# esq_ordenado.net
KiCad netlist of a schematic drawn in EAGLE
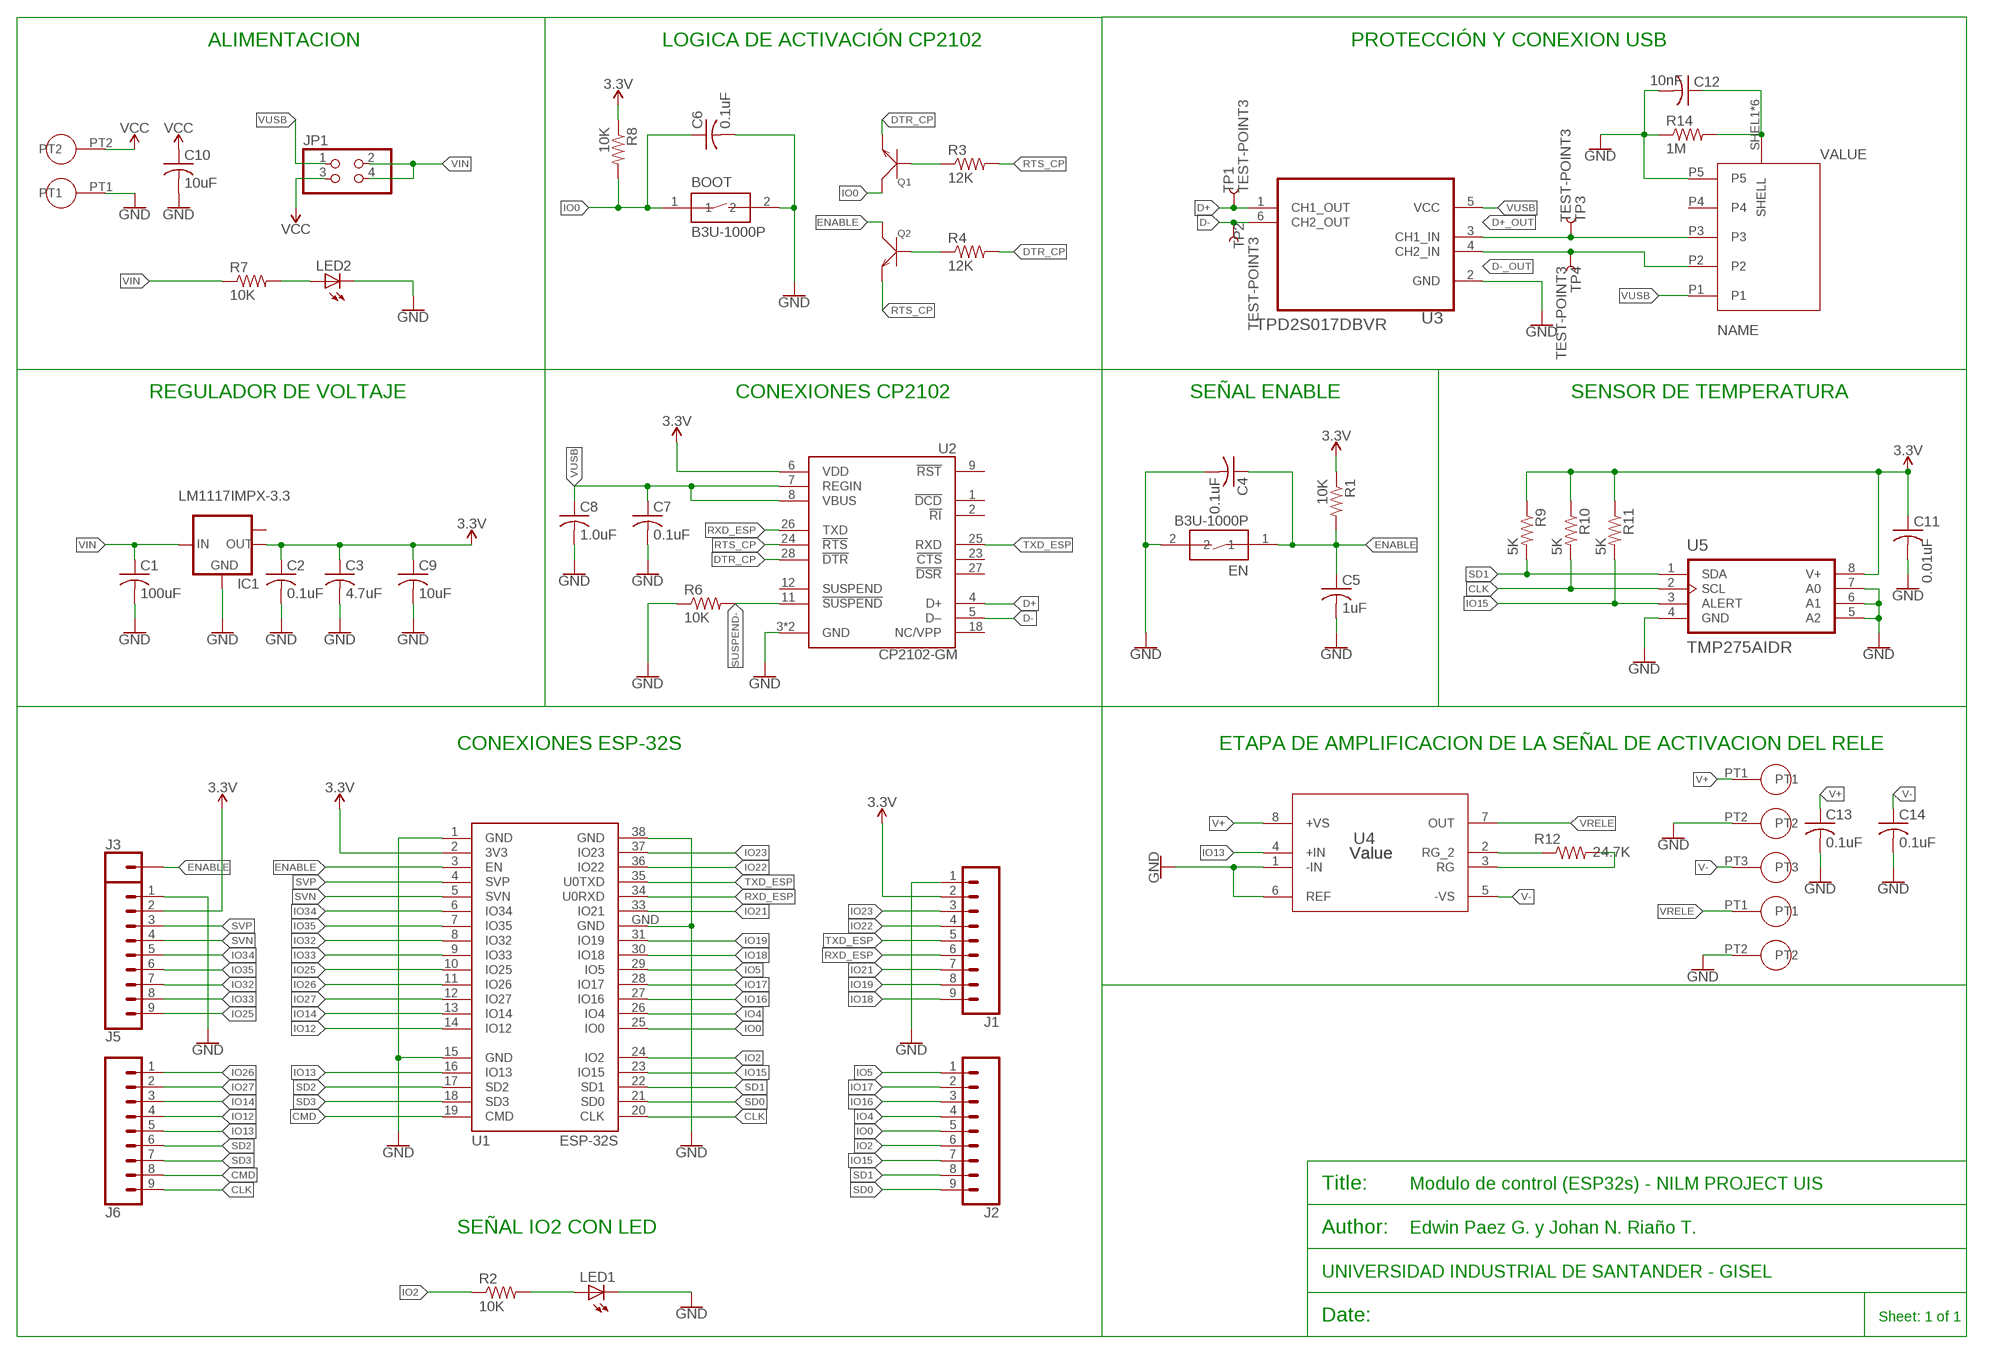
[diagram p0: schematic, sheet 1]

(export (version "E")
  (design (tool "Eeschema 10.0.6"))
  (components
    (comp (ref "BOOT")
      (value "B3U-1000P")
      (footprint "eagle-import:B3U-1000P")
      (fields
        (field (name "DIGI_KEY_PART_NUMBER") "SW1020CT-ND")
        (field (name "MANUFACTURER") "Omron Electronics Inc-EMC Div")
        (field (name "CREATED_BY") "PCBLayout.com")
      )
      (libsource (lib "eagle-import") (part "B3U-1000P"))
    )
    (comp (ref "C1")
      (value "100uF")
      (footprint "eagle-import:C0805")
      (libsource (lib "eagle-import") (part "C-USC0805"))
    )
    (comp (ref "C2")
      (value "0.1uF")
      (footprint "eagle-import:C0805")
      (libsource (lib "eagle-import") (part "C-USC0805"))
    )
    (comp (ref "C3")
      (value "4.7uF")
      (footprint "eagle-import:C0805")
      (libsource (lib "eagle-import") (part "C-USC0805"))
    )
    (comp (ref "C4")
      (value "0.1uF")
      (footprint "eagle-import:C0805")
      (libsource (lib "eagle-import") (part "C-USC0805"))
    )
    (comp (ref "C5")
      (value "1uF")
      (footprint "eagle-import:C0805")
      (libsource (lib "eagle-import") (part "C-USC0805"))
    )
    (comp (ref "C6")
      (value "0.1uF")
      (footprint "eagle-import:C0805")
      (libsource (lib "eagle-import") (part "C-USC0805"))
    )
    (comp (ref "C7")
      (value "0.1uF")
      (footprint "eagle-import:C0805")
      (libsource (lib "eagle-import") (part "C-USC0805"))
    )
    (comp (ref "C8")
      (value "1.0uF")
      (footprint "eagle-import:C0805")
      (libsource (lib "eagle-import") (part "C-USC0805"))
    )
    (comp (ref "C9")
      (value "10uF")
      (footprint "eagle-import:C0805")
      (libsource (lib "eagle-import") (part "C-USC0805"))
    )
    (comp (ref "C10")
      (value "10uF")
      (footprint "eagle-import:C0805")
      (libsource (lib "eagle-import") (part "C-USC0805"))
    )
    (comp (ref "C11")
      (value "0.01uF")
      (footprint "eagle-import:C0805")
      (libsource (lib "eagle-import") (part "C-USC0805"))
    )
    (comp (ref "C12")
      (value "10nF")
      (footprint "eagle-import:C0805")
      (libsource (lib "eagle-import") (part "C-USC0805"))
    )
    (comp (ref "C13")
      (value "0.1uF")
      (footprint "eagle-import:C0805")
      (libsource (lib "eagle-import") (part "C-USC0805"))
    )
    (comp (ref "C14")
      (value "0.1uF")
      (footprint "eagle-import:C0805")
      (libsource (lib "eagle-import") (part "C-USC0805"))
    )
    (comp (ref "EN")
      (value "B3U-1000P")
      (footprint "eagle-import:B3U-1000P")
      (fields
        (field (name "DIGI_KEY_PART_NUMBER") "SW1020CT-ND")
        (field (name "MANUFACTURER") "Omron Electronics Inc-EMC Div")
        (field (name "CREATED_BY") "PCBLayout.com")
      )
      (libsource (lib "eagle-import") (part "B3U-1000P"))
    )
    (comp (ref "IC1")
      (value "LM1117IMPX-3.3")
      (footprint "eagle-import:SOT223")
      (libsource (lib "eagle-import") (part "LM1117IMPX-3.3"))
    )
    (comp (ref "J1")
      (value "CONN_09")
      (footprint "eagle-import:1X09")
      (libsource (lib "eagle-import") (part "CONN_09"))
    )
    (comp (ref "J2")
      (value "CONN_09")
      (footprint "eagle-import:1X09")
      (libsource (lib "eagle-import") (part "CONN_09"))
    )
    (comp (ref "J3")
      (value "CONN_01")
      (footprint "eagle-import:1X01")
      (libsource (lib "eagle-import") (part "CONN_01"))
    )
    (comp (ref "J5")
      (value "CONN_09")
      (footprint "eagle-import:1X09")
      (libsource (lib "eagle-import") (part "CONN_09"))
    )
    (comp (ref "J6")
      (value "CONN_09")
      (footprint "eagle-import:1X09")
      (libsource (lib "eagle-import") (part "CONN_09"))
    )
    (comp (ref "JP1")
      (value "PINHD-2X2")
      (footprint "eagle-import:2X02")
      (libsource (lib "eagle-import") (part "PINHD-2X2"))
    )
    (comp (ref "LED1")
      (value "LEDCHIPLED_0805")
      (footprint "eagle-import:CHIPLED_0805")
      (libsource (lib "eagle-import") (part "LEDCHIPLED_0805"))
    )
    (comp (ref "LED2")
      (value "LEDCHIPLED_0805")
      (footprint "eagle-import:CHIPLED_0805")
      (libsource (lib "eagle-import") (part "LEDCHIPLED_0805"))
    )
    (comp (ref "Q1")
      (value "SMD-TRANSISTORS-NPN-25V-500MW(SOT-23)")
      (footprint "eagle-import:SOT-23")
      (fields (field (name "MF") "Recom Power") (field (name "MP") "S8050"))
      (libsource (lib "eagle-import") (part "SMD-TRANSISTORS-NPN-25V-500MW(SOT-23)"))
    )
    (comp (ref "Q2")
      (value "SMD-TRANSISTORS-NPN-25V-500MW(SOT-23)")
      (footprint "eagle-import:SOT-23")
      (fields (field (name "MF") "Recom Power") (field (name "MP") "S8050"))
      (libsource (lib "eagle-import") (part "SMD-TRANSISTORS-NPN-25V-500MW(SOT-23)"))
    )
    (comp (ref "R1")
      (value "10K")
      (footprint "eagle-import:R0805")
      (libsource (lib "eagle-import") (part "R-US_R0805"))
    )
    (comp (ref "R2")
      (value "10K")
      (footprint "eagle-import:R0805")
      (libsource (lib "eagle-import") (part "R-US_R0805"))
    )
    (comp (ref "R3")
      (value "12K")
      (footprint "eagle-import:R0805")
      (libsource (lib "eagle-import") (part "R-US_R0805"))
    )
    (comp (ref "R4")
      (value "12K")
      (footprint "eagle-import:R0805")
      (libsource (lib "eagle-import") (part "R-US_R0805"))
    )
    (comp (ref "R6")
      (value "10K")
      (footprint "eagle-import:R0805")
      (libsource (lib "eagle-import") (part "R-US_R0805"))
    )
    (comp (ref "R7")
      (value "10K")
      (footprint "eagle-import:R0805")
      (libsource (lib "eagle-import") (part "R-US_R0805"))
    )
    (comp (ref "R8")
      (value "10K")
      (footprint "eagle-import:R0805")
      (libsource (lib "eagle-import") (part "R-US_R0805"))
    )
    (comp (ref "R9")
      (value "5K")
      (footprint "eagle-import:R0805")
      (libsource (lib "eagle-import") (part "R-US_R0805"))
    )
    (comp (ref "R10")
      (value "5K")
      (footprint "eagle-import:R0805")
      (libsource (lib "eagle-import") (part "R-US_R0805"))
    )
    (comp (ref "R11")
      (value "5K")
      (footprint "eagle-import:R0805")
      (libsource (lib "eagle-import") (part "R-US_R0805"))
    )
    (comp (ref "R12")
      (value "24.7K")
      (footprint "eagle-import:R0805")
      (libsource (lib "eagle-import") (part "R-US_R0805"))
    )
    (comp (ref "R14")
      (value "1M")
      (footprint "eagle-import:R0805")
      (libsource (lib "eagle-import") (part "R-US_R0805"))
    )
    (comp (ref "TP1")
      (value "TEST-POINT3")
      (footprint "eagle-import:PAD.03X.03")
      (libsource (lib "eagle-import") (part "TEST-POINT3"))
    )
    (comp (ref "TP2")
      (value "TEST-POINT3")
      (footprint "eagle-import:PAD.03X.03")
      (libsource (lib "eagle-import") (part "TEST-POINT3"))
    )
    (comp (ref "TP3")
      (value "TEST-POINT3")
      (footprint "eagle-import:PAD.03X.03")
      (libsource (lib "eagle-import") (part "TEST-POINT3"))
    )
    (comp (ref "TP4")
      (value "TEST-POINT3")
      (footprint "eagle-import:PAD.03X.03")
      (libsource (lib "eagle-import") (part "TEST-POINT3"))
    )
    (comp (ref "U$1")
      (value "MICRO_USB_B-AMPHENOL(10118192)")
      (footprint "eagle-import:MICRO_B_10118192")
      (libsource (lib "eagle-import") (part "MICRO_USB_B-AMPHENOL(10118192)"))
    )
    (comp (ref "U$2")
      (value "PT2,5/2-5,0")
      (footprint "eagle-import:PT2,5_2-5,0")
      (libsource (lib "eagle-import") (part "PT2,5/2-5,0"))
    )
    (comp (ref "U$3")
      (value "PT2,5/2-5,0")
      (footprint "eagle-import:PT2,5_2-5,0")
      (libsource (lib "eagle-import") (part "PT2,5/2-5,0"))
    )
    (comp (ref "U$4")
      (value "PT2,5/3-5,0")
      (footprint "eagle-import:PT2,5_3-5,0")
      (libsource (lib "eagle-import") (part "PT2,5/3-5,0"))
    )
    (comp (ref "U1")
      (value "ESP-32S")
      (footprint "eagle-import:ESP-32S")
      (libsource (lib "eagle-import") (part "ESP-32S"))
    )
    (comp (ref "U2")
      (value "CP2102-GM")
      (footprint "eagle-import:QFN50P500X500X100-29N")
      (fields (field (name "MF") "Silicon Labs"))
      (libsource (lib "eagle-import") (part "CP2102-GM"))
    )
    (comp (ref "U3")
      (value "TPD2S017DBVR")
      (footprint "eagle-import:SOT95P280X145-6N")
      (fields (field (name "DIGI-KEY_PART_NUMBER") "296-25216-1-ND") (field (name "MF") "Texas Instruments"))
      (libsource (lib "eagle-import") (part "TPD2S017DBVR"))
    )
    (comp (ref "U4")
      (value "Value")
      (footprint "eagle-import:D0008A_M")
      (fields (field (name "MANUFACTURER") "Texas Instruments") (field (name "PARTNUMBER") "INA821ID"))
      (libsource (lib "eagle-import") (part "INA821IDD0008A_M"))
    )
    (comp (ref "U5")
      (value "TMP275AIDR")
      (footprint "eagle-import:TMP275AIDR")
      (fields
        (field (name "DIGIKEY_PART_NUMBER") "296-39296-2-ND")
        (field (name "MANUFACTURER") "Texas Instruments")
        (field (name "CREATED_BY") "PCBLayout.com")
      )
      (libsource (lib "eagle-import") (part "TMP275AIDR"))
    )
  )
  (nets
    (net (code "1") (name "3.3V") (class "Default")
      (node (ref "C11") (pin "1") (pinfunction "1_1") (pintype "passive"))
      (node (ref "C2") (pin "1") (pinfunction "1_1") (pintype "passive"))
      (node (ref "C3") (pin "1") (pinfunction "1_1") (pintype "passive"))
      (node (ref "C9") (pin "1") (pinfunction "1_1") (pintype "passive"))
      (node (ref "IC1") (pin "2") (pinfunction "OUT_2") (pintype "passive"))
      (node (ref "J1") (pin "2") (pinfunction "2_2") (pintype "passive"))
      (node (ref "J5") (pin "2") (pinfunction "2_2") (pintype "passive"))
      (node (ref "R1") (pin "1") (pinfunction "1_1") (pintype "passive"))
      (node (ref "R10") (pin "1") (pinfunction "1_1") (pintype "passive"))
      (node (ref "R11") (pin "1") (pinfunction "1_1") (pintype "passive"))
      (node (ref "R8") (pin "1") (pinfunction "1_1") (pintype "passive"))
      (node (ref "R9") (pin "1") (pinfunction "1_1") (pintype "passive"))
      (node (ref "U1") (pin "2") (pinfunction "3V3_2") (pintype "power_in"))
      (node (ref "U2") (pin "6") (pinfunction "VDD_6") (pintype "power_in"))
      (node (ref "U5") (pin "8") (pinfunction "V+_8") (pintype "input"))
    )
    (net (code "2") (name "CLK") (class "Default")
      (node (ref "J6") (pin "9") (pinfunction "9_9") (pintype "passive"))
      (node (ref "R10") (pin "2") (pinfunction "2_2") (pintype "passive"))
      (node (ref "U1") (pin "20") (pinfunction "CLK_20") (pintype "bidirectional"))
      (node (ref "U5") (pin "2") (pinfunction "SCL_2") (pintype "input"))
    )
    (net (code "3") (name "CMD") (class "Default")
      (node (ref "J6") (pin "8") (pinfunction "8_8") (pintype "passive"))
      (node (ref "U1") (pin "19") (pinfunction "CMD_19") (pintype "bidirectional"))
    )
    (net (code "4") (name "D+") (class "Default")
      (node (ref "TP1") (pin "P$1") (pinfunction "1_P$1") (pintype "bidirectional"))
      (node (ref "U2") (pin "4") (pinfunction "D+_4") (pintype "bidirectional"))
      (node (ref "U3") (pin "1") (pinfunction "CH1_OUT_1") (pintype "output"))
    )
    (net (code "5") (name "D+_OUT") (class "Default")
      (node (ref "TP3") (pin "P$1") (pinfunction "1_P$1") (pintype "bidirectional"))
      (node (ref "U$1") (pin "P3") (pinfunction "P3_P3") (pintype "bidirectional"))
      (node (ref "U3") (pin "3") (pinfunction "CH1_IN_3") (pintype "input"))
    )
    (net (code "6") (name "D-") (class "Default")
      (node (ref "TP2") (pin "P$1") (pinfunction "1_P$1") (pintype "bidirectional"))
      (node (ref "U2") (pin "5") (pinfunction "D–_5") (pintype "bidirectional"))
      (node (ref "U3") (pin "6") (pinfunction "CH2_OUT_6") (pintype "output"))
    )
    (net (code "7") (name "D-_OUT") (class "Default")
      (node (ref "TP4") (pin "P$1") (pinfunction "1_P$1") (pintype "bidirectional"))
      (node (ref "U$1") (pin "P2") (pinfunction "P2_P2") (pintype "bidirectional"))
      (node (ref "U3") (pin "4") (pinfunction "CH2_IN_4") (pintype "input"))
    )
    (net (code "8") (name "DTR_CP") (class "Default")
      (node (ref "Q1") (pin "2") (pinfunction "E_2") (pintype "passive"))
      (node (ref "R4") (pin "2") (pinfunction "2_2") (pintype "passive"))
      (node (ref "U2") (pin "28") (pinfunction "~{DTR}_28") (pintype "output"))
    )
    (net (code "9") (name "ENABLE") (class "Default")
      (node (ref "C4") (pin "1") (pinfunction "1_1") (pintype "passive"))
      (node (ref "C5") (pin "1") (pinfunction "1_1") (pintype "passive"))
      (node (ref "EN") (pin "1") (pinfunction "1_1") (pintype "passive"))
      (node (ref "J3") (pin "1") (pinfunction "1_1") (pintype "passive"))
      (node (ref "Q2") (pin "3") (pinfunction "C_3") (pintype "passive"))
      (node (ref "R1") (pin "2") (pinfunction "2_2") (pintype "passive"))
      (node (ref "U1") (pin "3") (pinfunction "EN_3") (pintype "input"))
    )
    (net (code "10") (name "GND") (class "Default")
      (node (ref "BOOT") (pin "2") (pinfunction "2_2") (pintype "passive"))
      (node (ref "C1") (pin "2") (pinfunction "2_2") (pintype "passive"))
      (node (ref "C10") (pin "2") (pinfunction "2_2") (pintype "passive"))
      (node (ref "C11") (pin "2") (pinfunction "2_2") (pintype "passive"))
      (node (ref "C12") (pin "2") (pinfunction "2_2") (pintype "passive"))
      (node (ref "C13") (pin "2") (pinfunction "2_2") (pintype "passive"))
      (node (ref "C14") (pin "2") (pinfunction "2_2") (pintype "passive"))
      (node (ref "C2") (pin "2") (pinfunction "2_2") (pintype "passive"))
      (node (ref "C3") (pin "2") (pinfunction "2_2") (pintype "passive"))
      (node (ref "C4") (pin "2") (pinfunction "2_2") (pintype "passive"))
      (node (ref "C5") (pin "2") (pinfunction "2_2") (pintype "passive"))
      (node (ref "C6") (pin "2") (pinfunction "2_2") (pintype "passive"))
      (node (ref "C7") (pin "2") (pinfunction "2_2") (pintype "passive"))
      (node (ref "C8") (pin "2") (pinfunction "2_2") (pintype "passive"))
      (node (ref "C9") (pin "2") (pinfunction "2_2") (pintype "passive"))
      (node (ref "EN") (pin "2") (pinfunction "2_2") (pintype "passive"))
      (node (ref "IC1") (pin "1") (pinfunction "GND_1") (pintype "input"))
      (node (ref "J1") (pin "1") (pinfunction "1_1") (pintype "passive"))
      (node (ref "J5") (pin "1") (pinfunction "1_1") (pintype "passive"))
      (node (ref "LED1") (pin "C") (pinfunction "C_C") (pintype "passive"))
      (node (ref "LED2") (pin "C") (pinfunction "C_C") (pintype "passive"))
      (node (ref "R14") (pin "1") (pinfunction "1_1") (pintype "passive"))
      (node (ref "R6") (pin "1") (pinfunction "1_1") (pintype "passive"))
      (node (ref "U$1") (pin "P5") (pinfunction "P5_P5") (pintype "bidirectional"))
      (node (ref "U$2") (pin "PT1") (pinfunction "PT1_PT1") (pintype "bidirectional"))
      (node (ref "U$3") (pin "PT2") (pinfunction "PT2_PT2") (pintype "bidirectional"))
      (node (ref "U$4") (pin "PT2") (pinfunction "PT2_PT2") (pintype "bidirectional"))
      (node (ref "U1") (pin "1") (pinfunction "GND_1") (pintype "power_in"))
      (node (ref "U1") (pin "15") (pinfunction "GND_15") (pintype "power_in"))
      (node (ref "U1") (pin "38") (pinfunction "GND_38") (pintype "power_in"))
      (node (ref "U1") (pin "GND") (pinfunction "GND_GND") (pintype "power_in"))
      (node (ref "U2") (pin "29") (pinfunction "GND_29") (pintype "power_in"))
      (node (ref "U2") (pin "3") (pinfunction "GND_3") (pintype "power_in"))
      (node (ref "U3") (pin "2") (pinfunction "GND_2") (pintype "passive"))
      (node (ref "U4") (pin "1") (pinfunction "-IN_1") (pintype "input"))
      (node (ref "U4") (pin "6") (pinfunction "REF_6") (pintype "input"))
      (node (ref "U5") (pin "4") (pinfunction "GND_4") (pintype "power_in"))
      (node (ref "U5") (pin "5") (pinfunction "A2_5") (pintype "input"))
      (node (ref "U5") (pin "6") (pinfunction "A1_6") (pintype "input"))
      (node (ref "U5") (pin "7") (pinfunction "A0_7") (pintype "input"))
    )
    (net (code "11") (name "IO0") (class "Default")
      (node (ref "BOOT") (pin "1") (pinfunction "1_1") (pintype "passive"))
      (node (ref "C6") (pin "1") (pinfunction "1_1") (pintype "passive"))
      (node (ref "J2") (pin "5") (pinfunction "5_5") (pintype "passive"))
      (node (ref "Q1") (pin "3") (pinfunction "C_3") (pintype "passive"))
      (node (ref "R8") (pin "2") (pinfunction "2_2") (pintype "passive"))
      (node (ref "U1") (pin "25") (pinfunction "IO0_25") (pintype "bidirectional"))
    )
    (net (code "12") (name "IO2") (class "Default")
      (node (ref "J2") (pin "6") (pinfunction "6_6") (pintype "passive"))
      (node (ref "R2") (pin "1") (pinfunction "1_1") (pintype "passive"))
      (node (ref "U1") (pin "24") (pinfunction "IO2_24") (pintype "bidirectional"))
    )
    (net (code "13") (name "IO4") (class "Default")
      (node (ref "J2") (pin "4") (pinfunction "4_4") (pintype "passive"))
      (node (ref "U1") (pin "26") (pinfunction "IO4_26") (pintype "bidirectional"))
    )
    (net (code "14") (name "IO5") (class "Default")
      (node (ref "J2") (pin "1") (pinfunction "1_1") (pintype "passive"))
      (node (ref "U1") (pin "29") (pinfunction "IO5_29") (pintype "bidirectional"))
    )
    (net (code "15") (name "IO12") (class "Default")
      (node (ref "J6") (pin "4") (pinfunction "4_4") (pintype "passive"))
      (node (ref "U1") (pin "14") (pinfunction "IO12_14") (pintype "bidirectional"))
    )
    (net (code "16") (name "IO13") (class "Default")
      (node (ref "J6") (pin "5") (pinfunction "5_5") (pintype "passive"))
      (node (ref "U1") (pin "16") (pinfunction "IO13_16") (pintype "bidirectional"))
      (node (ref "U4") (pin "4") (pinfunction "+IN_4") (pintype "input"))
    )
    (net (code "17") (name "IO14") (class "Default")
      (node (ref "J6") (pin "3") (pinfunction "3_3") (pintype "passive"))
      (node (ref "U1") (pin "13") (pinfunction "IO14_13") (pintype "bidirectional"))
    )
    (net (code "18") (name "IO15") (class "Default")
      (node (ref "J2") (pin "7") (pinfunction "7_7") (pintype "passive"))
      (node (ref "R11") (pin "2") (pinfunction "2_2") (pintype "passive"))
      (node (ref "U1") (pin "23") (pinfunction "IO15_23") (pintype "bidirectional"))
      (node (ref "U5") (pin "3") (pinfunction "ALERT_3") (pintype "output"))
    )
    (net (code "19") (name "IO16") (class "Default")
      (node (ref "J2") (pin "3") (pinfunction "3_3") (pintype "passive"))
      (node (ref "U1") (pin "27") (pinfunction "IO16_27") (pintype "bidirectional"))
    )
    (net (code "20") (name "IO17") (class "Default")
      (node (ref "J2") (pin "2") (pinfunction "2_2") (pintype "passive"))
      (node (ref "U1") (pin "28") (pinfunction "IO17_28") (pintype "bidirectional"))
    )
    (net (code "21") (name "IO18") (class "Default")
      (node (ref "J1") (pin "9") (pinfunction "9_9") (pintype "passive"))
      (node (ref "U1") (pin "30") (pinfunction "IO18_30") (pintype "bidirectional"))
    )
    (net (code "22") (name "IO19") (class "Default")
      (node (ref "J1") (pin "8") (pinfunction "8_8") (pintype "passive"))
      (node (ref "U1") (pin "31") (pinfunction "IO19_31") (pintype "bidirectional"))
    )
    (net (code "23") (name "IO21") (class "Default")
      (node (ref "J1") (pin "7") (pinfunction "7_7") (pintype "passive"))
      (node (ref "U1") (pin "33") (pinfunction "IO21_33") (pintype "bidirectional"))
    )
    (net (code "24") (name "IO22") (class "Default")
      (node (ref "J1") (pin "4") (pinfunction "4_4") (pintype "passive"))
      (node (ref "U1") (pin "36") (pinfunction "IO22_36") (pintype "bidirectional"))
    )
    (net (code "25") (name "IO23") (class "Default")
      (node (ref "J1") (pin "3") (pinfunction "3_3") (pintype "passive"))
      (node (ref "U1") (pin "37") (pinfunction "IO23_37") (pintype "bidirectional"))
    )
    (net (code "26") (name "IO25") (class "Default")
      (node (ref "J5") (pin "9") (pinfunction "9_9") (pintype "passive"))
      (node (ref "U1") (pin "10") (pinfunction "IO25_10") (pintype "bidirectional"))
    )
    (net (code "27") (name "IO26") (class "Default")
      (node (ref "J6") (pin "1") (pinfunction "1_1") (pintype "passive"))
      (node (ref "U1") (pin "11") (pinfunction "IO26_11") (pintype "bidirectional"))
    )
    (net (code "28") (name "IO27") (class "Default")
      (node (ref "J6") (pin "2") (pinfunction "2_2") (pintype "passive"))
      (node (ref "U1") (pin "12") (pinfunction "IO27_12") (pintype "bidirectional"))
    )
    (net (code "29") (name "IO32") (class "Default")
      (node (ref "J5") (pin "7") (pinfunction "7_7") (pintype "passive"))
      (node (ref "U1") (pin "8") (pinfunction "IO32_8") (pintype "bidirectional"))
    )
    (net (code "30") (name "IO33") (class "Default")
      (node (ref "J5") (pin "8") (pinfunction "8_8") (pintype "passive"))
      (node (ref "U1") (pin "9") (pinfunction "IO33_9") (pintype "bidirectional"))
    )
    (net (code "31") (name "IO34") (class "Default")
      (node (ref "J5") (pin "5") (pinfunction "5_5") (pintype "passive"))
      (node (ref "U1") (pin "6") (pinfunction "IO34_6") (pintype "bidirectional"))
    )
    (net (code "32") (name "IO35") (class "Default")
      (node (ref "J5") (pin "6") (pinfunction "6_6") (pintype "passive"))
      (node (ref "U1") (pin "7") (pinfunction "IO35_7") (pintype "bidirectional"))
    )
    (net (code "33") (name "Net-(C12-Pad1)") (class "Default")
      (node (ref "C12") (pin "1") (pinfunction "1_1") (pintype "passive"))
      (node (ref "R14") (pin "2") (pinfunction "2_2") (pintype "passive"))
      (node (ref "U$1") (pin "SHEL1") (pinfunction "SHELL_SHEL1") (pintype "bidirectional"))
      (node (ref "U$1") (pin "SHEL2") (pinfunction "SHELL_SHEL2") (pintype "bidirectional"))
      (node (ref "U$1") (pin "SHEL3") (pinfunction "SHELL_SHEL3") (pintype "bidirectional"))
      (node (ref "U$1") (pin "SHEL4") (pinfunction "SHELL_SHEL4") (pintype "bidirectional"))
      (node (ref "U$1") (pin "SHEL5") (pinfunction "SHELL_SHEL5") (pintype "bidirectional"))
      (node (ref "U$1") (pin "SHEL6") (pinfunction "SHELL_SHEL6") (pintype "bidirectional"))
    )
    (net (code "34") (name "Net-(LED1-PadA)") (class "Default")
      (node (ref "LED1") (pin "A") (pinfunction "A_A") (pintype "passive"))
      (node (ref "R2") (pin "2") (pinfunction "2_2") (pintype "passive"))
    )
    (net (code "35") (name "Net-(LED2-PadA)") (class "Default")
      (node (ref "LED2") (pin "A") (pinfunction "A_A") (pintype "passive"))
      (node (ref "R7") (pin "2") (pinfunction "2_2") (pintype "passive"))
    )
    (net (code "36") (name "Net-(Q1-B)") (class "Default")
      (node (ref "Q1") (pin "1") (pinfunction "B_1") (pintype "passive"))
      (node (ref "R3") (pin "1") (pinfunction "1_1") (pintype "passive"))
    )
    (net (code "37") (name "Net-(Q2-B)") (class "Default")
      (node (ref "Q2") (pin "1") (pinfunction "B_1") (pintype "passive"))
      (node (ref "R4") (pin "1") (pinfunction "1_1") (pintype "passive"))
    )
    (net (code "38") (name "Net-(U4-RG)") (class "Default")
      (node (ref "R12") (pin "2") (pinfunction "2_2") (pintype "passive"))
      (node (ref "U4") (pin "3") (pinfunction "RG_3") (pintype "input"))
    )
    (net (code "39") (name "Net-(U4-RG_2)") (class "Default")
      (node (ref "R12") (pin "1") (pinfunction "1_1") (pintype "passive"))
      (node (ref "U4") (pin "2") (pinfunction "RG_2_2") (pintype "input"))
    )
    (net (code "40") (name "RTS_CP") (class "Default")
      (node (ref "Q2") (pin "2") (pinfunction "E_2") (pintype "passive"))
      (node (ref "R3") (pin "2") (pinfunction "2_2") (pintype "passive"))
      (node (ref "U2") (pin "24") (pinfunction "~{RTS}_24") (pintype "output"))
    )
    (net (code "41") (name "RXD_ESP") (class "Default")
      (node (ref "J1") (pin "6") (pinfunction "6_6") (pintype "passive"))
      (node (ref "U1") (pin "34") (pinfunction "U0RXD_34") (pintype "bidirectional"))
      (node (ref "U2") (pin "26") (pinfunction "TXD_26") (pintype "output"))
    )
    (net (code "42") (name "SD0") (class "Default")
      (node (ref "J2") (pin "9") (pinfunction "9_9") (pintype "passive"))
      (node (ref "U1") (pin "21") (pinfunction "SD0_21") (pintype "bidirectional"))
    )
    (net (code "43") (name "SD1") (class "Default")
      (node (ref "J2") (pin "8") (pinfunction "8_8") (pintype "passive"))
      (node (ref "R9") (pin "2") (pinfunction "2_2") (pintype "passive"))
      (node (ref "U1") (pin "22") (pinfunction "SD1_22") (pintype "bidirectional"))
      (node (ref "U5") (pin "1") (pinfunction "SDA_1") (pintype "bidirectional"))
    )
    (net (code "44") (name "SD2") (class "Default")
      (node (ref "J6") (pin "6") (pinfunction "6_6") (pintype "passive"))
      (node (ref "U1") (pin "17") (pinfunction "SD2_17") (pintype "bidirectional"))
    )
    (net (code "45") (name "SD3") (class "Default")
      (node (ref "J6") (pin "7") (pinfunction "7_7") (pintype "passive"))
      (node (ref "U1") (pin "18") (pinfunction "SD3_18") (pintype "bidirectional"))
    )
    (net (code "46") (name "SUSPEND-") (class "Default")
      (node (ref "R6") (pin "2") (pinfunction "2_2") (pintype "passive"))
      (node (ref "U2") (pin "11") (pinfunction "~{SUSPEND}_11") (pintype "output"))
    )
    (net (code "47") (name "SVN") (class "Default")
      (node (ref "J5") (pin "4") (pinfunction "4_4") (pintype "passive"))
      (node (ref "U1") (pin "5") (pinfunction "SVN_5") (pintype "bidirectional"))
    )
    (net (code "48") (name "SVP") (class "Default")
      (node (ref "J5") (pin "3") (pinfunction "3_3") (pintype "passive"))
      (node (ref "U1") (pin "4") (pinfunction "SVP_4") (pintype "bidirectional"))
    )
    (net (code "49") (name "TXD_ESP") (class "Default")
      (node (ref "J1") (pin "5") (pinfunction "5_5") (pintype "passive"))
      (node (ref "U1") (pin "35") (pinfunction "U0TXD_35") (pintype "bidirectional"))
      (node (ref "U2") (pin "25") (pinfunction "RXD_25") (pintype "input"))
    )
    (net (code "50") (name "V+") (class "Default")
      (node (ref "C13") (pin "1") (pinfunction "1_1") (pintype "passive"))
      (node (ref "U$4") (pin "PT1") (pinfunction "PT1_PT1") (pintype "bidirectional"))
      (node (ref "U4") (pin "8") (pinfunction "+VS_8") (pintype "power_in"))
    )
    (net (code "51") (name "V-") (class "Default")
      (node (ref "C14") (pin "1") (pinfunction "1_1") (pintype "passive"))
      (node (ref "U$4") (pin "PT3") (pinfunction "PT3_PT3") (pintype "bidirectional"))
      (node (ref "U4") (pin "5") (pinfunction "-VS_5") (pintype "power_in"))
    )
    (net (code "52") (name "VCC") (class "Default")
      (node (ref "C10") (pin "1") (pinfunction "1_1") (pintype "passive"))
      (node (ref "JP1") (pin "3") (pinfunction "3_3") (pintype "passive"))
      (node (ref "U$2") (pin "PT2") (pinfunction "PT2_PT2") (pintype "bidirectional"))
    )
    (net (code "53") (name "VIN") (class "Default")
      (node (ref "C1") (pin "1") (pinfunction "1_1") (pintype "passive"))
      (node (ref "IC1") (pin "3") (pinfunction "IN_3") (pintype "input"))
      (node (ref "JP1") (pin "2") (pinfunction "2_2") (pintype "passive"))
      (node (ref "JP1") (pin "4") (pinfunction "4_4") (pintype "passive"))
      (node (ref "R7") (pin "1") (pinfunction "1_1") (pintype "passive"))
    )
    (net (code "54") (name "VRELE") (class "Default")
      (node (ref "U$3") (pin "PT1") (pinfunction "PT1_PT1") (pintype "bidirectional"))
      (node (ref "U4") (pin "7") (pinfunction "OUT_7") (pintype "output"))
    )
    (net (code "55") (name "VUSB") (class "Default")
      (node (ref "C7") (pin "1") (pinfunction "1_1") (pintype "passive"))
      (node (ref "C8") (pin "1") (pinfunction "1_1") (pintype "passive"))
      (node (ref "JP1") (pin "1") (pinfunction "1_1") (pintype "passive"))
      (node (ref "U$1") (pin "P1") (pinfunction "P1_P1") (pintype "bidirectional"))
      (node (ref "U2") (pin "7") (pinfunction "REGIN_7") (pintype "power_in"))
      (node (ref "U2") (pin "8") (pinfunction "VBUS_8") (pintype "power_in"))
      (node (ref "U3") (pin "5") (pinfunction "VCC_5") (pintype "power_in"))
    )
    (net (code "56") (name "unconnected-(IC1-OUT1-PadTAB)") (class "Default")
      (node (ref "IC1") (pin "TAB") (pinfunction "OUT1_TAB") (pintype "passive"))
    )
    (net (code "57") (name "unconnected-(U$1-PadP4)") (class "Default")
      (node (ref "U$1") (pin "P4") (pinfunction "P4_P4") (pintype "bidirectional"))
    )
    (net (code "58") (name "unconnected-(U2-NC{slash}VPP-Pad18)") (class "Default")
      (node (ref "U2") (pin "18") (pinfunction "NC/VPP_18") (pintype "bidirectional"))
    )
    (net (code "59") (name "unconnected-(U2-SUSPEND-Pad12)") (class "Default")
      (node (ref "U2") (pin "12") (pinfunction "SUSPEND_12") (pintype "output"))
    )
    (net (code "60") (name "unconnected-(U2-~{CTS}-Pad23)") (class "Default")
      (node (ref "U2") (pin "23") (pinfunction "~{CTS}_23") (pintype "input"))
    )
    (net (code "61") (name "unconnected-(U2-~{DCD}-Pad1)") (class "Default")
      (node (ref "U2") (pin "1") (pinfunction "~{DCD}_1") (pintype "input"))
    )
    (net (code "62") (name "unconnected-(U2-~{DSR}-Pad27)") (class "Default")
      (node (ref "U2") (pin "27") (pinfunction "~{DSR}_27") (pintype "input"))
    )
    (net (code "63") (name "unconnected-(U2-~{RI}-Pad2)") (class "Default")
      (node (ref "U2") (pin "2") (pinfunction "~{RI}_2") (pintype "input"))
    )
    (net (code "64") (name "unconnected-(U2-~{RST}-Pad9)") (class "Default")
      (node (ref "U2") (pin "9") (pinfunction "~{RST}_9") (pintype "bidirectional"))
    )
  )
)
